# Sheet_1.net
KiCad netlist of a schematic drawn in EasyEDA
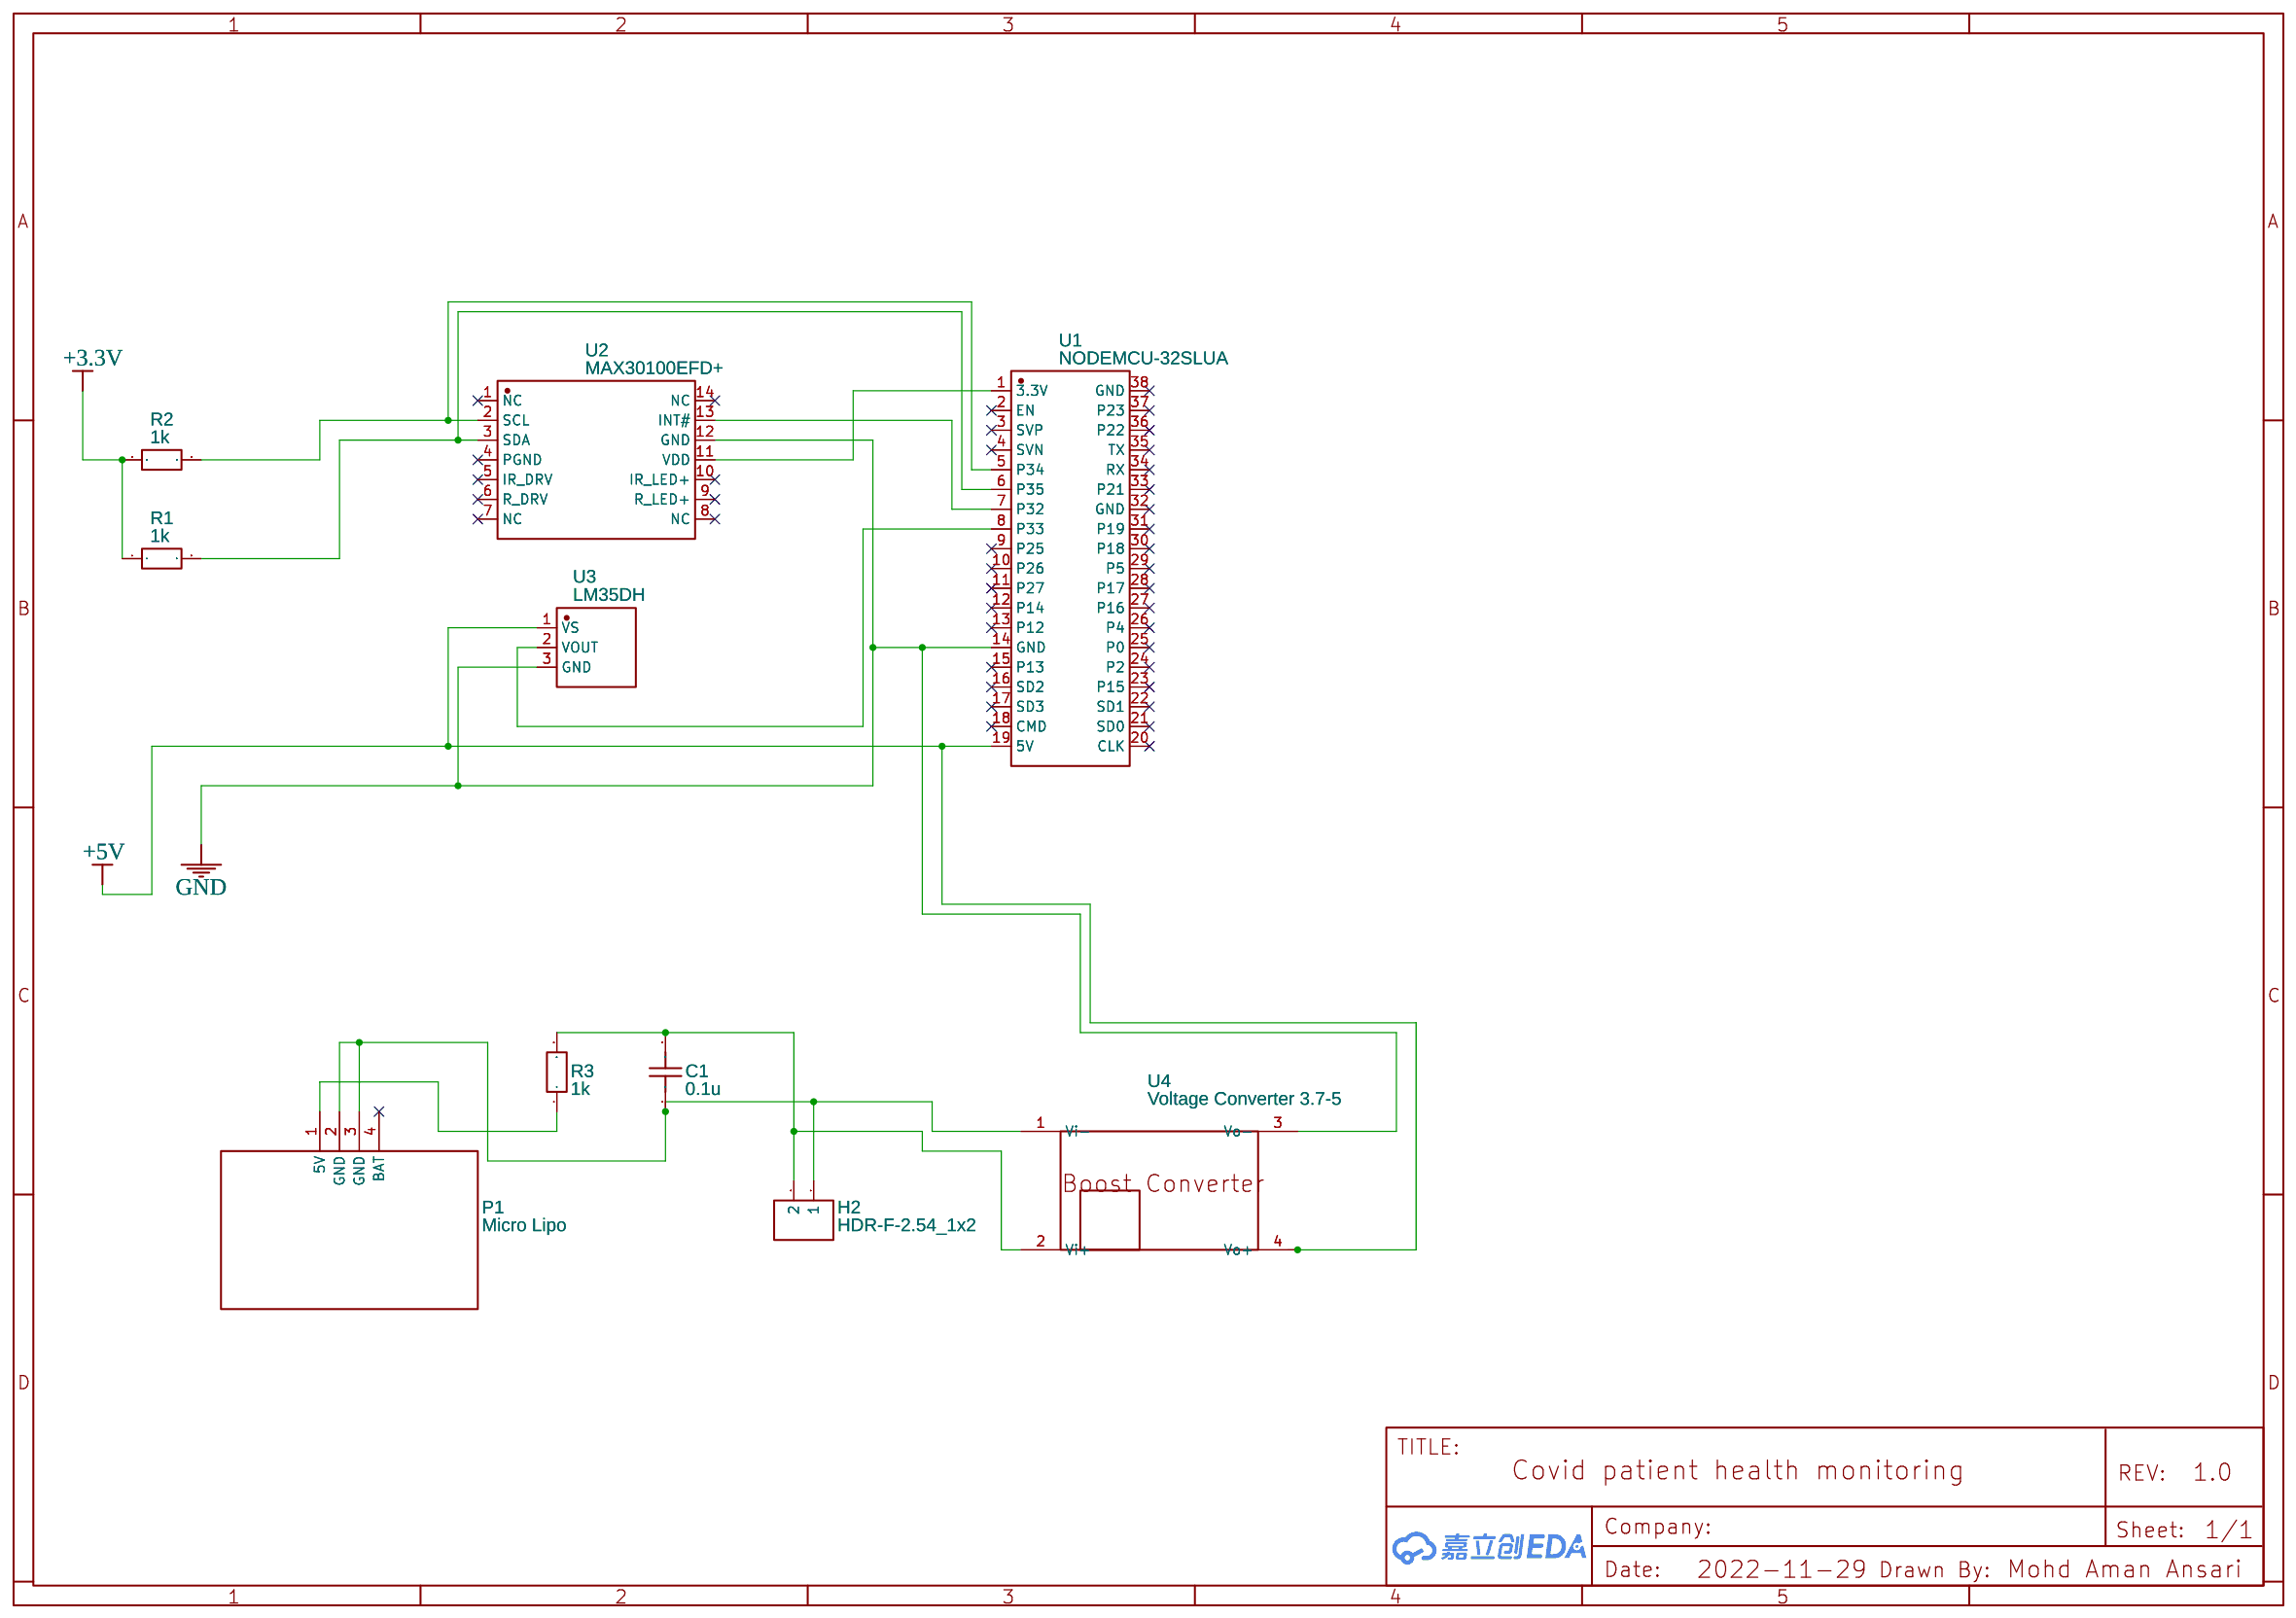
[diagram p0: schematic sheet]

(export (version "E")
  (design (tool "Eeschema 10.0.6"))
  (components
    (comp (ref "C1") (value "0.1u") (libsource (lib "") (part "C_0603_US")))
    (comp (ref "H2")
      (value "HDR-F-2.54_1x2")
      (fields (field (name "BOM_Supplier Part") "C49661"))
      (libsource (lib "") (part "HDR-F-2.54_1x2"))
    )
    (comp (ref "P1") (value "Micro Lipo") (libsource (lib "") (part "Micro Lipo")))
    (comp (ref "R1") (value "1k") (libsource (lib "") (part "R_0603_EU")))
    (comp (ref "R2") (value "1k") (libsource (lib "") (part "R_0603_EU")))
    (comp (ref "R3") (value "1k") (libsource (lib "") (part "R_0603_EU_1")))
    (comp (ref "U1")
      (value "NODEMCU-32SLUA")
      (fields
        (field (name "BOM_Manufacturer Part") "NodeMCU-32SLua")
        (field (name "BOM_Supplier Part") "C111436")
      )
      (libsource (lib "") (part "NODEMCU-32SLUA"))
    )
    (comp (ref "U2")
      (value "MAX30100EFD+")
      (fields (field (name "BOM_Supplier Part") "C92512"))
      (libsource (lib "") (part "MAX30100EFD+"))
    )
    (comp (ref "U3")
      (value "LM35DH")
      (fields (field (name "BOM_Supplier Part") "C2869869"))
      (libsource (lib "") (part "LM35DH"))
    )
    (comp (ref "U4") (value "Voltage Converter 3.7-5") (libsource (lib "") (part "Voltage Converter 3.7-5")))
  )
  (nets
    (net (code "1") (name "+3.3V") (class "Default")
      (node (ref "R1") (pin "1") (pinfunction "1_1") (pintype "unspecified"))
      (node (ref "R2") (pin "1") (pinfunction "1_1") (pintype "unspecified"))
    )
    (net (code "2") (name "+5V") (class "Default")
      (node (ref "U1") (pin "19") (pinfunction "5V_19") (pintype "unspecified"))
      (node (ref "U3") (pin "1") (pinfunction "VS_1") (pintype "unspecified"))
      (node (ref "U4") (pin "4") (pinfunction "Vo+_4") (pintype "unspecified"))
    )
    (net (code "3") (name "GND") (class "Default")
      (node (ref "U1") (pin "14") (pinfunction "GND_14") (pintype "unspecified"))
      (node (ref "U2") (pin "12") (pinfunction "GND_12") (pintype "unspecified"))
      (node (ref "U3") (pin "3") (pinfunction "GND_3") (pintype "unspecified"))
      (node (ref "U4") (pin "3") (pinfunction "Vo-_3") (pintype "unspecified"))
    )
    (net (code "4") (name "Net-(P1-5V)") (class "Default")
      (node (ref "P1") (pin "1") (pinfunction "5V_1") (pintype "unspecified"))
      (node (ref "R3") (pin "1") (pinfunction "1_1") (pintype "unspecified"))
    )
    (net (code "5") (name "Net-(U1-3.3V)") (class "Default")
      (node (ref "U1") (pin "1") (pinfunction "3.3V_1") (pintype "unspecified"))
      (node (ref "U2") (pin "11") (pinfunction "VDD_11") (pintype "unspecified"))
    )
    (net (code "6") (name "Net-(U1-P32)") (class "Default")
      (node (ref "U1") (pin "7") (pinfunction "P32_7") (pintype "unspecified"))
      (node (ref "U2") (pin "13") (pinfunction "INT#_13") (pintype "unspecified"))
    )
    (net (code "7") (name "Net-(U1-P33)") (class "Default")
      (node (ref "U1") (pin "8") (pinfunction "P33_8") (pintype "unspecified"))
      (node (ref "U3") (pin "2") (pinfunction "VOUT_2") (pintype "unspecified"))
    )
    (net (code "8") (name "Net-(U1-P34)") (class "Default")
      (node (ref "R2") (pin "2") (pinfunction "2_2") (pintype "unspecified"))
      (node (ref "U1") (pin "5") (pinfunction "P34_5") (pintype "unspecified"))
      (node (ref "U2") (pin "2") (pinfunction "SCL_2") (pintype "unspecified"))
    )
    (net (code "9") (name "Net-(U1-P35)") (class "Default")
      (node (ref "R1") (pin "2") (pinfunction "2_2") (pintype "unspecified"))
      (node (ref "U1") (pin "6") (pinfunction "P35_6") (pintype "unspecified"))
      (node (ref "U2") (pin "3") (pinfunction "SDA_3") (pintype "unspecified"))
    )
    (net (code "10") (name "Net-(U4-Vi+)") (class "Default")
      (node (ref "C1") (pin "2") (pinfunction "2_2") (pintype "unspecified"))
      (node (ref "H2") (pin "2") (pinfunction "2_2") (pintype "input"))
      (node (ref "R3") (pin "2") (pinfunction "2_2") (pintype "unspecified"))
      (node (ref "U4") (pin "2") (pinfunction "Vi+_2") (pintype "unspecified"))
    )
    (net (code "11") (name "Net-(U4-Vi-)") (class "Default")
      (node (ref "C1") (pin "1") (pinfunction "1_1") (pintype "unspecified"))
      (node (ref "H2") (pin "1") (pinfunction "1_1") (pintype "input"))
      (node (ref "P1") (pin "2") (pinfunction "GND_2") (pintype "unspecified"))
      (node (ref "P1") (pin "3") (pinfunction "GND_3") (pintype "unspecified"))
      (node (ref "U4") (pin "1") (pinfunction "Vi-_1") (pintype "unspecified"))
    )
    (net (code "12") (name "unconnected-(P1-BAT-Pad4)") (class "Default")
      (node (ref "P1") (pin "4") (pinfunction "BAT_4") (pintype "unspecified+no_connect"))
    )
    (net (code "13") (name "unconnected-(U1-CLK-Pad20)") (class "Default")
      (node (ref "U1") (pin "20") (pinfunction "CLK_20") (pintype "unspecified+no_connect"))
    )
    (net (code "14") (name "unconnected-(U1-CMD-Pad18)") (class "Default")
      (node (ref "U1") (pin "18") (pinfunction "CMD_18") (pintype "unspecified+no_connect"))
    )
    (net (code "15") (name "unconnected-(U1-EN-Pad2)") (class "Default")
      (node (ref "U1") (pin "2") (pinfunction "EN_2") (pintype "unspecified+no_connect"))
    )
    (net (code "16") (name "unconnected-(U1-GND-Pad32)") (class "Default")
      (node (ref "U1") (pin "32") (pinfunction "GND_32") (pintype "unspecified+no_connect"))
    )
    (net (code "17") (name "unconnected-(U1-GND-Pad38)") (class "Default")
      (node (ref "U1") (pin "38") (pinfunction "GND_38") (pintype "unspecified+no_connect"))
    )
    (net (code "18") (name "unconnected-(U1-P0-Pad25)") (class "Default")
      (node (ref "U1") (pin "25") (pinfunction "P0_25") (pintype "unspecified+no_connect"))
    )
    (net (code "19") (name "unconnected-(U1-P2-Pad24)") (class "Default")
      (node (ref "U1") (pin "24") (pinfunction "P2_24") (pintype "unspecified+no_connect"))
    )
    (net (code "20") (name "unconnected-(U1-P4-Pad26)") (class "Default")
      (node (ref "U1") (pin "26") (pinfunction "P4_26") (pintype "unspecified+no_connect"))
    )
    (net (code "21") (name "unconnected-(U1-P5-Pad29)") (class "Default")
      (node (ref "U1") (pin "29") (pinfunction "P5_29") (pintype "unspecified+no_connect"))
    )
    (net (code "22") (name "unconnected-(U1-P12-Pad13)") (class "Default")
      (node (ref "U1") (pin "13") (pinfunction "P12_13") (pintype "unspecified+no_connect"))
    )
    (net (code "23") (name "unconnected-(U1-P13-Pad15)") (class "Default")
      (node (ref "U1") (pin "15") (pinfunction "P13_15") (pintype "unspecified+no_connect"))
    )
    (net (code "24") (name "unconnected-(U1-P14-Pad12)") (class "Default")
      (node (ref "U1") (pin "12") (pinfunction "P14_12") (pintype "unspecified+no_connect"))
    )
    (net (code "25") (name "unconnected-(U1-P15-Pad23)") (class "Default")
      (node (ref "U1") (pin "23") (pinfunction "P15_23") (pintype "unspecified+no_connect"))
    )
    (net (code "26") (name "unconnected-(U1-P16-Pad27)") (class "Default")
      (node (ref "U1") (pin "27") (pinfunction "P16_27") (pintype "unspecified+no_connect"))
    )
    (net (code "27") (name "unconnected-(U1-P17-Pad28)") (class "Default")
      (node (ref "U1") (pin "28") (pinfunction "P17_28") (pintype "unspecified+no_connect"))
    )
    (net (code "28") (name "unconnected-(U1-P18-Pad30)") (class "Default")
      (node (ref "U1") (pin "30") (pinfunction "P18_30") (pintype "unspecified+no_connect"))
    )
    (net (code "29") (name "unconnected-(U1-P19-Pad31)") (class "Default")
      (node (ref "U1") (pin "31") (pinfunction "P19_31") (pintype "unspecified+no_connect"))
    )
    (net (code "30") (name "unconnected-(U1-P21-Pad33)") (class "Default")
      (node (ref "U1") (pin "33") (pinfunction "P21_33") (pintype "unspecified+no_connect"))
    )
    (net (code "31") (name "unconnected-(U1-P22-Pad36)") (class "Default")
      (node (ref "U1") (pin "36") (pinfunction "P22_36") (pintype "unspecified+no_connect"))
    )
    (net (code "32") (name "unconnected-(U1-P23-Pad37)") (class "Default")
      (node (ref "U1") (pin "37") (pinfunction "P23_37") (pintype "unspecified+no_connect"))
    )
    (net (code "33") (name "unconnected-(U1-P25-Pad9)") (class "Default")
      (node (ref "U1") (pin "9") (pinfunction "P25_9") (pintype "unspecified+no_connect"))
    )
    (net (code "34") (name "unconnected-(U1-P26-Pad10)") (class "Default")
      (node (ref "U1") (pin "10") (pinfunction "P26_10") (pintype "unspecified+no_connect"))
    )
    (net (code "35") (name "unconnected-(U1-P27-Pad11)") (class "Default")
      (node (ref "U1") (pin "11") (pinfunction "P27_11") (pintype "unspecified+no_connect"))
    )
    (net (code "36") (name "unconnected-(U1-RX-Pad34)") (class "Default")
      (node (ref "U1") (pin "34") (pinfunction "RX_34") (pintype "unspecified+no_connect"))
    )
    (net (code "37") (name "unconnected-(U1-SD0-Pad21)") (class "Default")
      (node (ref "U1") (pin "21") (pinfunction "SD0_21") (pintype "unspecified+no_connect"))
    )
    (net (code "38") (name "unconnected-(U1-SD1-Pad22)") (class "Default")
      (node (ref "U1") (pin "22") (pinfunction "SD1_22") (pintype "unspecified+no_connect"))
    )
    (net (code "39") (name "unconnected-(U1-SD2-Pad16)") (class "Default")
      (node (ref "U1") (pin "16") (pinfunction "SD2_16") (pintype "unspecified+no_connect"))
    )
    (net (code "40") (name "unconnected-(U1-SD3-Pad17)") (class "Default")
      (node (ref "U1") (pin "17") (pinfunction "SD3_17") (pintype "unspecified+no_connect"))
    )
    (net (code "41") (name "unconnected-(U1-SVN-Pad4)") (class "Default")
      (node (ref "U1") (pin "4") (pinfunction "SVN_4") (pintype "unspecified+no_connect"))
    )
    (net (code "42") (name "unconnected-(U1-SVP-Pad3)") (class "Default")
      (node (ref "U1") (pin "3") (pinfunction "SVP_3") (pintype "unspecified+no_connect"))
    )
    (net (code "43") (name "unconnected-(U1-TX-Pad35)") (class "Default")
      (node (ref "U1") (pin "35") (pinfunction "TX_35") (pintype "unspecified+no_connect"))
    )
    (net (code "44") (name "unconnected-(U2-IR_DRV-Pad5)") (class "Default")
      (node (ref "U2") (pin "5") (pinfunction "IR_DRV_5") (pintype "unspecified+no_connect"))
    )
    (net (code "45") (name "unconnected-(U2-IR_LED+-Pad10)") (class "Default")
      (node (ref "U2") (pin "10") (pinfunction "IR_LED+_10") (pintype "unspecified+no_connect"))
    )
    (net (code "46") (name "unconnected-(U2-NC-Pad1)") (class "Default")
      (node (ref "U2") (pin "1") (pinfunction "NC_1") (pintype "unspecified+no_connect"))
    )
    (net (code "47") (name "unconnected-(U2-NC-Pad7)") (class "Default")
      (node (ref "U2") (pin "7") (pinfunction "NC_7") (pintype "unspecified+no_connect"))
    )
    (net (code "48") (name "unconnected-(U2-NC-Pad8)") (class "Default")
      (node (ref "U2") (pin "8") (pinfunction "NC_8") (pintype "unspecified+no_connect"))
    )
    (net (code "49") (name "unconnected-(U2-NC-Pad14)") (class "Default")
      (node (ref "U2") (pin "14") (pinfunction "NC_14") (pintype "unspecified+no_connect"))
    )
    (net (code "50") (name "unconnected-(U2-PGND-Pad4)") (class "Default")
      (node (ref "U2") (pin "4") (pinfunction "PGND_4") (pintype "unspecified+no_connect"))
    )
    (net (code "51") (name "unconnected-(U2-R_DRV-Pad6)") (class "Default")
      (node (ref "U2") (pin "6") (pinfunction "R_DRV_6") (pintype "unspecified+no_connect"))
    )
    (net (code "52") (name "unconnected-(U2-R_LED+-Pad9)") (class "Default")
      (node (ref "U2") (pin "9") (pinfunction "R_LED+_9") (pintype "unspecified+no_connect"))
    )
  )
)
